# Power_Supply.net
KiCad netlist of a schematic drawn in Altium Designer
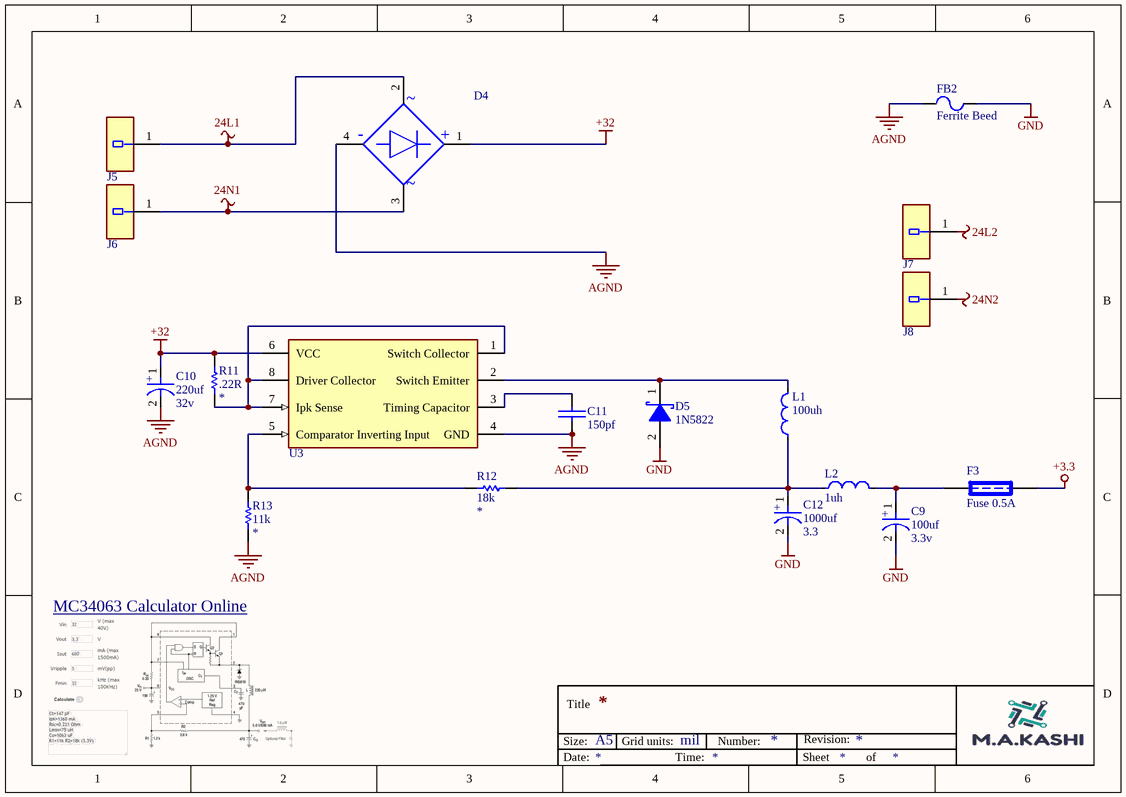
[diagram p0: Power Supply.SchDoc]

(export (version "E")
  (design (tool "Eeschema 10.0.6"))
  (components
    (comp (ref "C9")
      (value "Capacitor Electrolytic")
      (footprint "CAP_electrolitic_8.3x10_Panasonic")
      (fields (field (name "CAPACITANCE") "100uf") (field (name "VOLTAGE") "3.3v"))
      (libsource (lib "E-component") (part "Capacitor Electrolytic"))
    )
    (comp (ref "C10")
      (value "Capacitor Electrolytic")
      (footprint "CAP_electrolitic_8.3x10_Panasonic")
      (fields (field (name "CAPACITANCE") "220uf") (field (name "VOLTAGE") "32v"))
      (libsource (lib "E-component") (part "Capacitor Electrolytic"))
    )
    (comp (ref "C11")
      (value "150pf")
      (footprint "cap_0805_A")
      (description "octopart or digikey description!")
      (libsource (lib "E-component") (part "Capacitor"))
    )
    (comp (ref "C12")
      (value "Capacitor Electrolytic")
      (footprint "CAP_electrolitic_10x10.2_Panasonic")
      (fields (field (name "CAPACITANCE") "1000uf") (field (name "VOLTAGE") "3.3"))
      (libsource (lib "E-component") (part "Capacitor Electrolytic"))
    )
    (comp (ref "D4")
      (value "Bridge Rectifier")
      (footprint "Bridge Rectifier_Vishay_GBU_MFG")
      (fields (field (name "PART NUMBER") "GBL406"))
      (libsource (lib "E-component") (part "Bridge Rectifier"))
    )
    (comp (ref "D5")
      (value "1N5822")
      (footprint "1N5822")
      (libsource (lib "E-component") (part "Schottky Diode"))
    )
    (comp (ref "F3")
      (value "Fuse 0.5A")
      (footprint "FUSE")
      (description "Fuse")
      (fields (field (name "PUBLISHER") "Altium Limited"))
      (libsource (lib "E-component") (part "Fuse"))
    )
    (comp (ref "FB2")
      (value "Ferrite Beed")
      (footprint "AXIAL-0.3")
      (fields (field (name "PUBLISHER") "Altium Limited"))
      (libsource (lib "E-component") (part "Ferrite Beed"))
    )
    (comp (ref "J5")
      (value "Quick-Fit")
      (footprint "Quick-Fit_Keystone_1287_0")
      (libsource (lib "E-component") (part "Quick-Fit"))
    )
    (comp (ref "J6")
      (value "Quick-Fit")
      (footprint "Quick-Fit_Keystone_1287_0")
      (libsource (lib "E-component") (part "Quick-Fit"))
    )
    (comp (ref "J7")
      (value "Quick-Fit")
      (footprint "Quick-Fit_Keystone_1287_0")
      (libsource (lib "E-component") (part "Quick-Fit"))
    )
    (comp (ref "J8")
      (value "Quick-Fit")
      (footprint "Quick-Fit_Keystone_1287_0")
      (libsource (lib "E-component") (part "Quick-Fit"))
    )
    (comp (ref "L1")
      (value "100uh")
      (footprint "INDUCTOR_SMD")
      (description "octopart or digikey description!")
      (fields (field (name "PART NUMBER") "NLV32T-101J-PF"))
      (libsource (lib "E-component") (part "Inductor"))
    )
    (comp (ref "L2")
      (value "1uh")
      (footprint "IND_DIP_7m")
      (description "octopart or digikey description!")
      (libsource (lib "E-component") (part "Inductor"))
    )
    (comp (ref "R11")
      (value ".22R")
      (footprint "RES_1206_A")
      (description "octopart or digikey description!")
      (fields (field (name "TOLERANCE") "*"))
      (libsource (lib "E-component") (part "Resistor"))
    )
    (comp (ref "R12")
      (value "18k")
      (footprint "RES_0805_A")
      (description "octopart or digikey description!")
      (fields (field (name "TOLERANCE") "*"))
      (libsource (lib "E-component") (part "Resistor"))
    )
    (comp (ref "R13")
      (value "11k")
      (footprint "RES_0805_A")
      (description "octopart or digikey description!")
      (fields (field (name "TOLERANCE") "*"))
      (libsource (lib "E-component") (part "Resistor"))
    )
    (comp (ref "U3")
      (value "MC33063ADR2G")
      (footprint "MC33063ADR2G_ON_Semiconductor_IPC_A")
      (libsource (lib "E-component") (part "MC33063ADR2G"))
    )
  )
  (nets
    (net (code "1") (name "+3.3") (class "Default")
      (node (ref "F3") (pin "2") (pinfunction "2_2") (pintype "passive"))
    )
    (net (code "2") (name "+32") (class "Default")
      (node (ref "C10") (pin "1") (pinfunction "C_1") (pintype "passive"))
      (node (ref "D4") (pin "1") (pinfunction "+_1") (pintype "passive"))
      (node (ref "R11") (pin "1") (pinfunction "1_1") (pintype "passive"))
      (node (ref "U3") (pin "6") (pinfunction "VCC_6") (pintype "power_in"))
    )
    (net (code "3") (name "24L1") (class "Default")
      (node (ref "D4") (pin "2") (pinfunction "1_~_2") (pintype "passive"))
      (node (ref "J5") (pin "1") (pinfunction "1_1") (pintype "passive"))
    )
    (net (code "4") (name "24L2") (class "Default")
      (node (ref "J7") (pin "1") (pinfunction "1_1") (pintype "passive"))
    )
    (net (code "5") (name "24N1") (class "Default")
      (node (ref "D4") (pin "3") (pinfunction "2_~_3") (pintype "passive"))
      (node (ref "J6") (pin "1") (pinfunction "1_1") (pintype "passive"))
    )
    (net (code "6") (name "24N2") (class "Default")
      (node (ref "J8") (pin "1") (pinfunction "1_1") (pintype "passive"))
    )
    (net (code "7") (name "AGND") (class "Default")
      (node (ref "C10") (pin "2") (pinfunction "A_2") (pintype "passive"))
      (node (ref "C11") (pin "2") (pinfunction "2_2") (pintype "passive"))
      (node (ref "D4") (pin "4") (pinfunction "-_4") (pintype "passive"))
      (node (ref "FB2") (pin "2") (pinfunction "2_2") (pintype "passive"))
      (node (ref "R13") (pin "2") (pinfunction "2_2") (pintype "passive"))
      (node (ref "U3") (pin "4") (pinfunction "GND_4") (pintype "power_in"))
    )
    (net (code "8") (name "GND") (class "Default")
      (node (ref "C12") (pin "2") (pinfunction "A_2") (pintype "passive"))
      (node (ref "C9") (pin "2") (pinfunction "A_2") (pintype "passive"))
      (node (ref "D5") (pin "2") (pinfunction "Anode_2") (pintype "passive"))
      (node (ref "FB2") (pin "1") (pinfunction "1_1") (pintype "passive"))
    )
    (net (code "9") (name "Net-(C9-C)") (class "Default")
      (node (ref "C9") (pin "1") (pinfunction "C_1") (pintype "passive"))
      (node (ref "F3") (pin "1") (pinfunction "1_1") (pintype "passive"))
      (node (ref "L2") (pin "2") (pinfunction "2_2") (pintype "passive"))
    )
    (net (code "10") (name "Net-(C12-C)") (class "Default")
      (node (ref "C12") (pin "1") (pinfunction "C_1") (pintype "passive"))
      (node (ref "L1") (pin "1") (pinfunction "1_1") (pintype "passive"))
      (node (ref "L2") (pin "1") (pinfunction "1_1") (pintype "passive"))
      (node (ref "R12") (pin "1") (pinfunction "1_1") (pintype "passive"))
    )
    (net (code "11") (name "Net-(D5-Cathode)") (class "Default")
      (node (ref "D5") (pin "1") (pinfunction "Cathode_1") (pintype "passive"))
      (node (ref "L1") (pin "2") (pinfunction "2_2") (pintype "passive"))
      (node (ref "U3") (pin "2") (pinfunction "Switch_Emitter_2") (pintype "open_emitter"))
    )
    (net (code "12") (name "Net-(U3-Comparator_Inverting_Input)") (class "Default")
      (node (ref "R12") (pin "2") (pinfunction "2_2") (pintype "passive"))
      (node (ref "R13") (pin "1") (pinfunction "1_1") (pintype "passive"))
      (node (ref "U3") (pin "5") (pinfunction "Comparator_Inverting_Input_5") (pintype "input"))
    )
    (net (code "13") (name "Net-(U3-Driver_Collector)") (class "Default")
      (node (ref "R11") (pin "2") (pinfunction "2_2") (pintype "passive"))
      (node (ref "U3") (pin "1") (pinfunction "Switch_Collector_1") (pintype "open_collector"))
      (node (ref "U3") (pin "7") (pinfunction "Ipk_Sense_7") (pintype "input"))
      (node (ref "U3") (pin "8") (pinfunction "Driver_Collector_8") (pintype "open_collector"))
    )
    (net (code "14") (name "Net-(U3-Timing_Capacitor)") (class "Default")
      (node (ref "C11") (pin "1") (pinfunction "1_1") (pintype "passive"))
      (node (ref "U3") (pin "3") (pinfunction "Timing_Capacitor_3") (pintype "passive"))
    )
  )
)
